# Top.net
KiCad netlist of a schematic drawn in Altium Designer
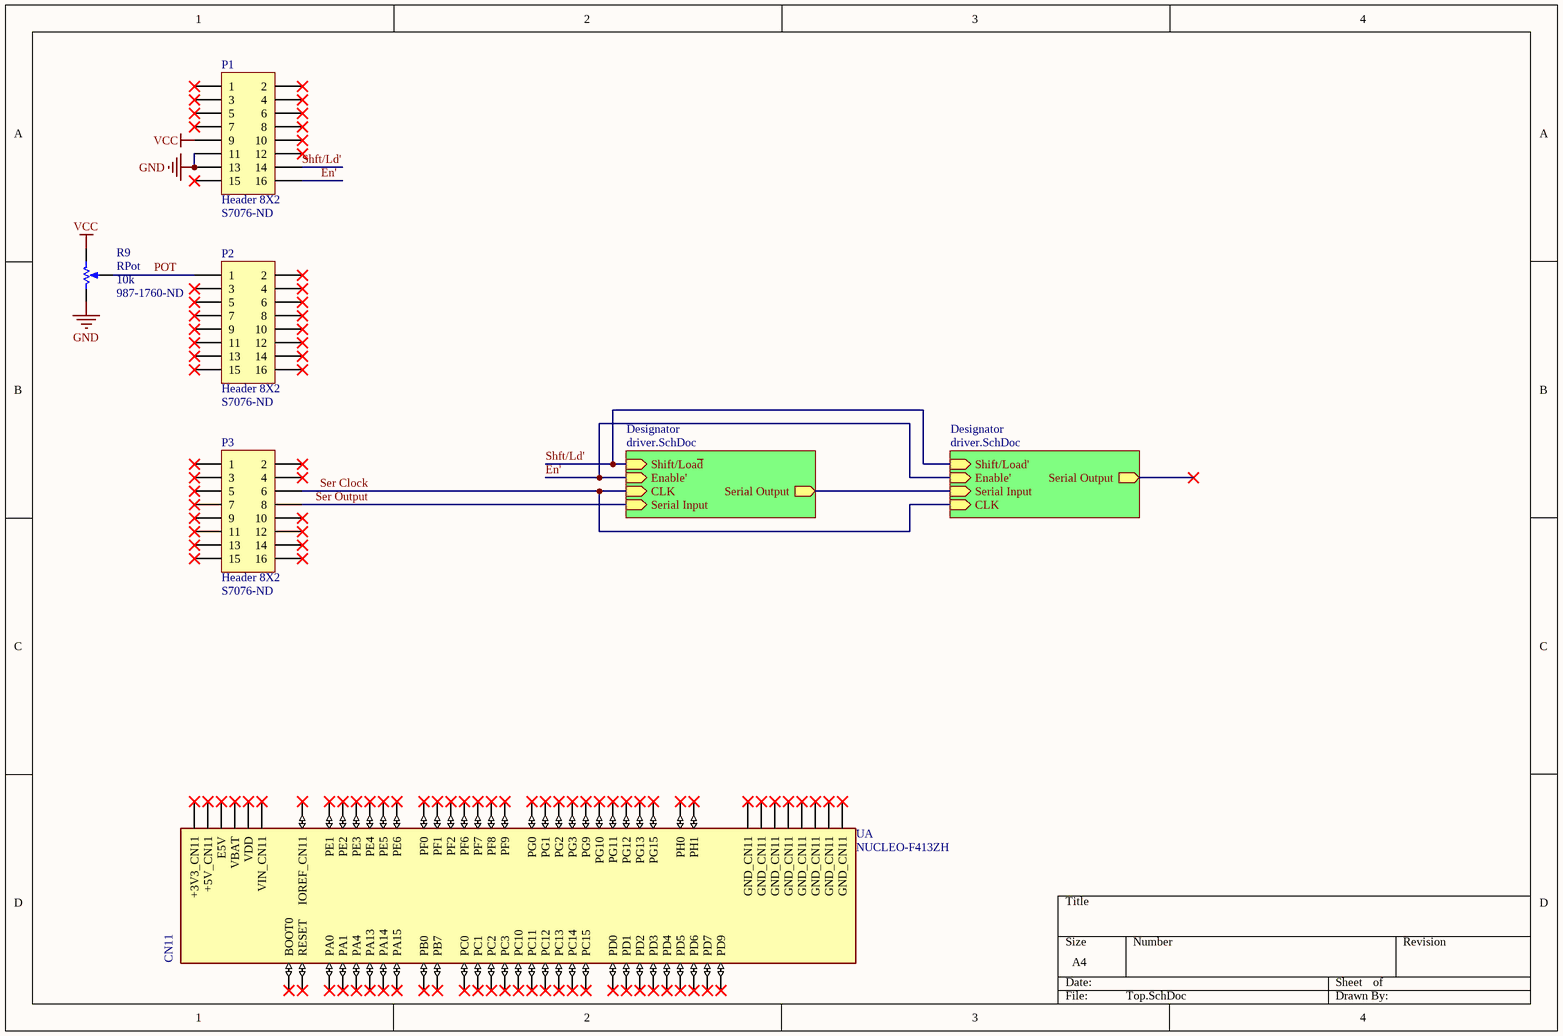
[diagram p0: Top.SchDoc]

(export (version "E")
  (design (tool "Eeschema 10.0.6"))
  (components
    (comp (ref "P1")
      (value "Header 8X2")
      (footprint "HDR2X8")
      (description "Header, 8-Pin, Dual row")
      (fields (field (name "SUPPLIER PART NUMBER 1") "S7076-ND") (field (name "PUBLISHER") "Altium Limited"))
      (libsource (lib "Miscellaneous Connectors") (part "Header 8X2"))
    )
    (comp (ref "P2")
      (value "Header 8X2")
      (footprint "HDR2X8")
      (description "Header, 8-Pin, Dual row")
      (fields (field (name "SUPPLIER PART NUMBER 1") "S7076-ND") (field (name "PUBLISHER") "Altium Limited"))
      (libsource (lib "Miscellaneous Connectors") (part "Header 8X2"))
    )
    (comp (ref "P3")
      (value "Header 8X2")
      (footprint "HDR2X8")
      (description "Header, 8-Pin, Dual row")
      (fields (field (name "SUPPLIER PART NUMBER 1") "S7076-ND") (field (name "PUBLISHER") "Altium Limited"))
      (libsource (lib "Miscellaneous Connectors") (part "Header 8X2"))
    )
    (comp (ref "R9")
      (value "RPot")
      (footprint "VR5")
      (description "Potentiometer")
      (fields
        (field (name "ALTIUM_VALUE") "10k")
        (field (name "SUPPLIER PART NUMBER 1") "987-1760-ND")
        (field (name "PUBLISHER") "Altium Limited")
      )
      (libsource (lib "Miscellaneous Devices") (part "RPot"))
    )
    (comp (ref "U")
      (value "NUCLEO-F413ZH")
      (footprint "ST_NUCLEO-F413ZH")
      (fields (field (name "MF") "STMicroelectronics"))
      (libsource (lib "NUCLEO-F413ZH") (part "NUCLEO-F413ZH"))
    )
  )
  (nets
    (net (code "1") (name "/En'") (class "Default")
      (node (ref "P1") (pin "16") (pinfunction "16_16") (pintype "passive"))
    )
    (net (code "2") (name "/POT") (class "Default")
      (node (ref "P2") (pin "1") (pinfunction "1_1") (pintype "passive"))
      (node (ref "R9") (pin "3") (pinfunction "TAP_3") (pintype "passive"))
    )
    (net (code "3") (name "/Ser Clock") (class "Default")
      (node (ref "P3") (pin "6") (pinfunction "6_6") (pintype "passive"))
    )
    (net (code "4") (name "/Ser Output") (class "Default")
      (node (ref "P3") (pin "8") (pinfunction "8_8") (pintype "passive"))
    )
    (net (code "7") (name "/Shft{slash}Ld'") (class "Default")
      (node (ref "P1") (pin "14") (pinfunction "14_14") (pintype "passive"))
    )
    (net (code "8") (name "GND") (class "Default")
      (node (ref "P1") (pin "11") (pinfunction "11_11") (pintype "passive"))
      (node (ref "P1") (pin "13") (pinfunction "13_13") (pintype "passive"))
      (node (ref "R9") (pin "2") (pinfunction "BOT_2") (pintype "passive"))
    )
    (net (code "9") (name "VCC") (class "Default")
      (node (ref "P1") (pin "9") (pinfunction "9_9") (pintype "passive"))
      (node (ref "R9") (pin "1") (pinfunction "TOP_1") (pintype "passive"))
    )
    (net (code "10") (name "unconnected-(P1-Pad1)") (class "Default")
      (node (ref "P1") (pin "1") (pinfunction "1_1") (pintype "passive+no_connect"))
    )
    (net (code "11") (name "unconnected-(P1-Pad2)") (class "Default")
      (node (ref "P1") (pin "2") (pinfunction "2_2") (pintype "passive+no_connect"))
    )
    (net (code "12") (name "unconnected-(P1-Pad3)") (class "Default")
      (node (ref "P1") (pin "3") (pinfunction "3_3") (pintype "passive+no_connect"))
    )
    (net (code "13") (name "unconnected-(P1-Pad4)") (class "Default")
      (node (ref "P1") (pin "4") (pinfunction "4_4") (pintype "passive+no_connect"))
    )
    (net (code "14") (name "unconnected-(P1-Pad5)") (class "Default")
      (node (ref "P1") (pin "5") (pinfunction "5_5") (pintype "passive+no_connect"))
    )
    (net (code "15") (name "unconnected-(P1-Pad6)") (class "Default")
      (node (ref "P1") (pin "6") (pinfunction "6_6") (pintype "passive+no_connect"))
    )
    (net (code "16") (name "unconnected-(P1-Pad7)") (class "Default")
      (node (ref "P1") (pin "7") (pinfunction "7_7") (pintype "passive+no_connect"))
    )
    (net (code "17") (name "unconnected-(P1-Pad8)") (class "Default")
      (node (ref "P1") (pin "8") (pinfunction "8_8") (pintype "passive+no_connect"))
    )
    (net (code "18") (name "unconnected-(P1-Pad10)") (class "Default")
      (node (ref "P1") (pin "10") (pinfunction "10_10") (pintype "passive+no_connect"))
    )
    (net (code "19") (name "unconnected-(P1-Pad12)") (class "Default")
      (node (ref "P1") (pin "12") (pinfunction "12_12") (pintype "passive+no_connect"))
    )
    (net (code "20") (name "unconnected-(P1-Pad15)") (class "Default")
      (node (ref "P1") (pin "15") (pinfunction "15_15") (pintype "passive+no_connect"))
    )
    (net (code "21") (name "unconnected-(P2-Pad2)") (class "Default")
      (node (ref "P2") (pin "2") (pinfunction "2_2") (pintype "passive+no_connect"))
    )
    (net (code "22") (name "unconnected-(P2-Pad3)") (class "Default")
      (node (ref "P2") (pin "3") (pinfunction "3_3") (pintype "passive+no_connect"))
    )
    (net (code "23") (name "unconnected-(P2-Pad4)") (class "Default")
      (node (ref "P2") (pin "4") (pinfunction "4_4") (pintype "passive+no_connect"))
    )
    (net (code "24") (name "unconnected-(P2-Pad5)") (class "Default")
      (node (ref "P2") (pin "5") (pinfunction "5_5") (pintype "passive+no_connect"))
    )
    (net (code "25") (name "unconnected-(P2-Pad6)") (class "Default")
      (node (ref "P2") (pin "6") (pinfunction "6_6") (pintype "passive+no_connect"))
    )
    (net (code "26") (name "unconnected-(P2-Pad7)") (class "Default")
      (node (ref "P2") (pin "7") (pinfunction "7_7") (pintype "passive+no_connect"))
    )
    (net (code "27") (name "unconnected-(P2-Pad8)") (class "Default")
      (node (ref "P2") (pin "8") (pinfunction "8_8") (pintype "passive+no_connect"))
    )
    (net (code "28") (name "unconnected-(P2-Pad9)") (class "Default")
      (node (ref "P2") (pin "9") (pinfunction "9_9") (pintype "passive+no_connect"))
    )
    (net (code "29") (name "unconnected-(P2-Pad10)") (class "Default")
      (node (ref "P2") (pin "10") (pinfunction "10_10") (pintype "passive+no_connect"))
    )
    (net (code "30") (name "unconnected-(P2-Pad11)") (class "Default")
      (node (ref "P2") (pin "11") (pinfunction "11_11") (pintype "passive+no_connect"))
    )
    (net (code "31") (name "unconnected-(P2-Pad12)") (class "Default")
      (node (ref "P2") (pin "12") (pinfunction "12_12") (pintype "passive+no_connect"))
    )
    (net (code "32") (name "unconnected-(P2-Pad13)") (class "Default")
      (node (ref "P2") (pin "13") (pinfunction "13_13") (pintype "passive+no_connect"))
    )
    (net (code "33") (name "unconnected-(P2-Pad14)") (class "Default")
      (node (ref "P2") (pin "14") (pinfunction "14_14") (pintype "passive+no_connect"))
    )
    (net (code "34") (name "unconnected-(P2-Pad15)") (class "Default")
      (node (ref "P2") (pin "15") (pinfunction "15_15") (pintype "passive+no_connect"))
    )
    (net (code "35") (name "unconnected-(P2-Pad16)") (class "Default")
      (node (ref "P2") (pin "16") (pinfunction "16_16") (pintype "passive+no_connect"))
    )
    (net (code "36") (name "unconnected-(P3-Pad1)") (class "Default")
      (node (ref "P3") (pin "1") (pinfunction "1_1") (pintype "passive+no_connect"))
    )
    (net (code "37") (name "unconnected-(P3-Pad2)") (class "Default")
      (node (ref "P3") (pin "2") (pinfunction "2_2") (pintype "passive+no_connect"))
    )
    (net (code "38") (name "unconnected-(P3-Pad3)") (class "Default")
      (node (ref "P3") (pin "3") (pinfunction "3_3") (pintype "passive+no_connect"))
    )
    (net (code "39") (name "unconnected-(P3-Pad4)") (class "Default")
      (node (ref "P3") (pin "4") (pinfunction "4_4") (pintype "passive+no_connect"))
    )
    (net (code "40") (name "unconnected-(P3-Pad5)") (class "Default")
      (node (ref "P3") (pin "5") (pinfunction "5_5") (pintype "passive+no_connect"))
    )
    (net (code "41") (name "unconnected-(P3-Pad7)") (class "Default")
      (node (ref "P3") (pin "7") (pinfunction "7_7") (pintype "passive+no_connect"))
    )
    (net (code "42") (name "unconnected-(P3-Pad9)") (class "Default")
      (node (ref "P3") (pin "9") (pinfunction "9_9") (pintype "passive+no_connect"))
    )
    (net (code "43") (name "unconnected-(P3-Pad10)") (class "Default")
      (node (ref "P3") (pin "10") (pinfunction "10_10") (pintype "passive+no_connect"))
    )
    (net (code "44") (name "unconnected-(P3-Pad11)") (class "Default")
      (node (ref "P3") (pin "11") (pinfunction "11_11") (pintype "passive+no_connect"))
    )
    (net (code "45") (name "unconnected-(P3-Pad12)") (class "Default")
      (node (ref "P3") (pin "12") (pinfunction "12_12") (pintype "passive+no_connect"))
    )
    (net (code "46") (name "unconnected-(P3-Pad13)") (class "Default")
      (node (ref "P3") (pin "13") (pinfunction "13_13") (pintype "passive+no_connect"))
    )
    (net (code "47") (name "unconnected-(P3-Pad14)") (class "Default")
      (node (ref "P3") (pin "14") (pinfunction "14_14") (pintype "passive+no_connect"))
    )
    (net (code "48") (name "unconnected-(P3-Pad15)") (class "Default")
      (node (ref "P3") (pin "15") (pinfunction "15_15") (pintype "passive+no_connect"))
    )
    (net (code "49") (name "unconnected-(P3-Pad16)") (class "Default")
      (node (ref "P3") (pin "16") (pinfunction "16_16") (pintype "passive+no_connect"))
    )
    (net (code "50") (name "unconnected-(UA-+3V3_CN11-PadCN11_16)") (class "Default")
      (node (ref "U") (pin "CN11_16") (pinfunction "+3V3_CN11_CN11_16") (pintype "power_in+no_connect"))
    )
    (net (code "51") (name "unconnected-(UA-+5V_CN11-PadCN11_18)") (class "Default")
      (node (ref "U") (pin "CN11_18") (pinfunction "+5V_CN11_CN11_18") (pintype "power_in+no_connect"))
    )
    (net (code "52") (name "unconnected-(UA-BOOT0-PadCN11_7)") (class "Default")
      (node (ref "U") (pin "CN11_7") (pinfunction "BOOT0_CN11_7") (pintype "bidirectional+no_connect"))
    )
    (net (code "53") (name "unconnected-(UA-E5V-PadCN11_6)") (class "Default")
      (node (ref "U") (pin "CN11_6") (pinfunction "E5V_CN11_6") (pintype "power_in+no_connect"))
    )
    (net (code "54") (name "unconnected-(UA-GND_CN11-PadCN11_8)") (class "Default")
      (node (ref "U") (pin "CN11_8") (pinfunction "GND_CN11_CN11_8") (pintype "power_in+no_connect"))
    )
    (net (code "55") (name "unconnected-(UA-GND_CN11-PadCN11_19)") (class "Default")
      (node (ref "U") (pin "CN11_19") (pinfunction "GND_CN11_CN11_19") (pintype "power_in+no_connect"))
    )
    (net (code "56") (name "unconnected-(UA-GND_CN11-PadCN11_20)") (class "Default")
      (node (ref "U") (pin "CN11_20") (pinfunction "GND_CN11_CN11_20") (pintype "power_in+no_connect"))
    )
    (net (code "57") (name "unconnected-(UA-GND_CN11-PadCN11_22)") (class "Default")
      (node (ref "U") (pin "CN11_22") (pinfunction "GND_CN11_CN11_22") (pintype "power_in+no_connect"))
    )
    (net (code "58") (name "unconnected-(UA-GND_CN11-PadCN11_49)") (class "Default")
      (node (ref "U") (pin "CN11_49") (pinfunction "GND_CN11_CN11_49") (pintype "power_in+no_connect"))
    )
    (net (code "59") (name "unconnected-(UA-GND_CN11-PadCN11_60)") (class "Default")
      (node (ref "U") (pin "CN11_60") (pinfunction "GND_CN11_CN11_60") (pintype "power_in+no_connect"))
    )
    (net (code "60") (name "unconnected-(UA-GND_CN11-PadCN11_71)") (class "Default")
      (node (ref "U") (pin "CN11_71") (pinfunction "GND_CN11_CN11_71") (pintype "power_in+no_connect"))
    )
    (net (code "61") (name "unconnected-(UA-GND_CN11-PadCN11_72)") (class "Default")
      (node (ref "U") (pin "CN11_72") (pinfunction "GND_CN11_CN11_72") (pintype "power_in+no_connect"))
    )
    (net (code "62") (name "unconnected-(UA-IOREF_CN11-PadCN11_12)") (class "Default")
      (node (ref "U") (pin "CN11_12") (pinfunction "IOREF_CN11_CN11_12") (pintype "bidirectional+no_connect"))
    )
    (net (code "63") (name "unconnected-(UA-PA0-PadCN11_28)") (class "Default")
      (node (ref "U") (pin "CN11_28") (pinfunction "PA0_CN11_28") (pintype "bidirectional+no_connect"))
    )
    (net (code "64") (name "unconnected-(UA-PA1-PadCN11_30)") (class "Default")
      (node (ref "U") (pin "CN11_30") (pinfunction "PA1_CN11_30") (pintype "bidirectional+no_connect"))
    )
    (net (code "65") (name "unconnected-(UA-PA4-PadCN11_32)") (class "Default")
      (node (ref "U") (pin "CN11_32") (pinfunction "PA4_CN11_32") (pintype "bidirectional+no_connect"))
    )
    (net (code "66") (name "unconnected-(UA-PA13-PadCN11_13)") (class "Default")
      (node (ref "U") (pin "CN11_13") (pinfunction "PA13_CN11_13") (pintype "bidirectional+no_connect"))
    )
    (net (code "67") (name "unconnected-(UA-PA14-PadCN11_15)") (class "Default")
      (node (ref "U") (pin "CN11_15") (pinfunction "PA14_CN11_15") (pintype "bidirectional+no_connect"))
    )
    (net (code "68") (name "unconnected-(UA-PA15-PadCN11_17)") (class "Default")
      (node (ref "U") (pin "CN11_17") (pinfunction "PA15_CN11_17") (pintype "bidirectional+no_connect"))
    )
    (net (code "69") (name "unconnected-(UA-PB0-PadCN11_34)") (class "Default")
      (node (ref "U") (pin "CN11_34") (pinfunction "PB0_CN11_34") (pintype "bidirectional+no_connect"))
    )
    (net (code "70") (name "unconnected-(UA-PB7-PadCN11_21)") (class "Default")
      (node (ref "U") (pin "CN11_21") (pinfunction "PB7_CN11_21") (pintype "bidirectional+no_connect"))
    )
    (net (code "71") (name "unconnected-(UA-PC0-PadCN11_38)") (class "Default")
      (node (ref "U") (pin "CN11_38") (pinfunction "PC0_CN11_38") (pintype "bidirectional+no_connect"))
    )
    (net (code "72") (name "unconnected-(UA-PC1-PadCN11_36)") (class "Default")
      (node (ref "U") (pin "CN11_36") (pinfunction "PC1_CN11_36") (pintype "bidirectional+no_connect"))
    )
    (net (code "73") (name "unconnected-(UA-PC2-PadCN11_35)") (class "Default")
      (node (ref "U") (pin "CN11_35") (pinfunction "PC2_CN11_35") (pintype "bidirectional+no_connect"))
    )
    (net (code "74") (name "unconnected-(UA-PC3-PadCN11_37)") (class "Default")
      (node (ref "U") (pin "CN11_37") (pinfunction "PC3_CN11_37") (pintype "bidirectional+no_connect"))
    )
    (net (code "75") (name "unconnected-(UA-PC10-PadCN11_1)") (class "Default")
      (node (ref "U") (pin "CN11_1") (pinfunction "PC10_CN11_1") (pintype "bidirectional+no_connect"))
    )
    (net (code "76") (name "unconnected-(UA-PC11-PadCN11_2)") (class "Default")
      (node (ref "U") (pin "CN11_2") (pinfunction "PC11_CN11_2") (pintype "bidirectional+no_connect"))
    )
    (net (code "77") (name "unconnected-(UA-PC12-PadCN11_3)") (class "Default")
      (node (ref "U") (pin "CN11_3") (pinfunction "PC12_CN11_3") (pintype "bidirectional+no_connect"))
    )
    (net (code "78") (name "unconnected-(UA-PC13-PadCN11_23)") (class "Default")
      (node (ref "U") (pin "CN11_23") (pinfunction "PC13_CN11_23") (pintype "bidirectional+no_connect"))
    )
    (net (code "79") (name "unconnected-(UA-PC14-PadCN11_25)") (class "Default")
      (node (ref "U") (pin "CN11_25") (pinfunction "PC14_CN11_25") (pintype "bidirectional+no_connect"))
    )
    (net (code "80") (name "unconnected-(UA-PC15-PadCN11_27)") (class "Default")
      (node (ref "U") (pin "CN11_27") (pinfunction "PC15_CN11_27") (pintype "bidirectional+no_connect"))
    )
    (net (code "81") (name "unconnected-(UA-PD0-PadCN11_57)") (class "Default")
      (node (ref "U") (pin "CN11_57") (pinfunction "PD0_CN11_57") (pintype "bidirectional+no_connect"))
    )
    (net (code "82") (name "unconnected-(UA-PD1-PadCN11_55)") (class "Default")
      (node (ref "U") (pin "CN11_55") (pinfunction "PD1_CN11_55") (pintype "bidirectional+no_connect"))
    )
    (net (code "83") (name "unconnected-(UA-PD2-PadCN11_4)") (class "Default")
      (node (ref "U") (pin "CN11_4") (pinfunction "PD2_CN11_4") (pintype "bidirectional+no_connect"))
    )
    (net (code "84") (name "unconnected-(UA-PD3-PadCN11_40)") (class "Default")
      (node (ref "U") (pin "CN11_40") (pinfunction "PD3_CN11_40") (pintype "bidirectional+no_connect"))
    )
    (net (code "85") (name "unconnected-(UA-PD4-PadCN11_39)") (class "Default")
      (node (ref "U") (pin "CN11_39") (pinfunction "PD4_CN11_39") (pintype "bidirectional+no_connect"))
    )
    (net (code "86") (name "unconnected-(UA-PD5-PadCN11_41)") (class "Default")
      (node (ref "U") (pin "CN11_41") (pinfunction "PD5_CN11_41") (pintype "bidirectional+no_connect"))
    )
    (net (code "87") (name "unconnected-(UA-PD6-PadCN11_43)") (class "Default")
      (node (ref "U") (pin "CN11_43") (pinfunction "PD6_CN11_43") (pintype "bidirectional+no_connect"))
    )
    (net (code "88") (name "unconnected-(UA-PD7-PadCN11_45)") (class "Default")
      (node (ref "U") (pin "CN11_45") (pinfunction "PD7_CN11_45") (pintype "bidirectional+no_connect"))
    )
    (net (code "89") (name "unconnected-(UA-PD9-PadCN11_69)") (class "Default")
      (node (ref "U") (pin "CN11_69") (pinfunction "PD9_CN11_69") (pintype "bidirectional+no_connect"))
    )
    (net (code "90") (name "unconnected-(UA-PE1-PadCN11_61)") (class "Default")
      (node (ref "U") (pin "CN11_61") (pinfunction "PE1_CN11_61") (pintype "bidirectional+no_connect"))
    )
    (net (code "91") (name "unconnected-(UA-PE2-PadCN11_46)") (class "Default")
      (node (ref "U") (pin "CN11_46") (pinfunction "PE2_CN11_46") (pintype "bidirectional+no_connect"))
    )
    (net (code "92") (name "unconnected-(UA-PE3-PadCN11_47)") (class "Default")
      (node (ref "U") (pin "CN11_47") (pinfunction "PE3_CN11_47") (pintype "bidirectional+no_connect"))
    )
    (net (code "93") (name "unconnected-(UA-PE4-PadCN11_48)") (class "Default")
      (node (ref "U") (pin "CN11_48") (pinfunction "PE4_CN11_48") (pintype "bidirectional+no_connect"))
    )
    (net (code "94") (name "unconnected-(UA-PE5-PadCN11_50)") (class "Default")
      (node (ref "U") (pin "CN11_50") (pinfunction "PE5_CN11_50") (pintype "bidirectional+no_connect"))
    )
    (net (code "95") (name "unconnected-(UA-PE6-PadCN11_62)") (class "Default")
      (node (ref "U") (pin "CN11_62") (pinfunction "PE6_CN11_62") (pintype "bidirectional+no_connect"))
    )
    (net (code "96") (name "unconnected-(UA-PF0-PadCN11_53)") (class "Default")
      (node (ref "U") (pin "CN11_53") (pinfunction "PF0_CN11_53") (pintype "bidirectional+no_connect"))
    )
    (net (code "97") (name "unconnected-(UA-PF1-PadCN11_51)") (class "Default")
      (node (ref "U") (pin "CN11_51") (pinfunction "PF1_CN11_51") (pintype "bidirectional+no_connect"))
    )
    (net (code "98") (name "unconnected-(UA-PF2-PadCN11_52)") (class "Default")
      (node (ref "U") (pin "CN11_52") (pinfunction "PF2_CN11_52") (pintype "bidirectional+no_connect"))
    )
    (net (code "99") (name "unconnected-(UA-PF6-PadCN11_9)") (class "Default")
      (node (ref "U") (pin "CN11_9") (pinfunction "PF6_CN11_9") (pintype "bidirectional+no_connect"))
    )
    (net (code "100") (name "unconnected-(UA-PF7-PadCN11_11)") (class "Default")
      (node (ref "U") (pin "CN11_11") (pinfunction "PF7_CN11_11") (pintype "bidirectional+no_connect"))
    )
    (net (code "101") (name "unconnected-(UA-PF8-PadCN11_54)") (class "Default")
      (node (ref "U") (pin "CN11_54") (pinfunction "PF8_CN11_54") (pintype "bidirectional+no_connect"))
    )
    (net (code "102") (name "unconnected-(UA-PF9-PadCN11_56)") (class "Default")
      (node (ref "U") (pin "CN11_56") (pinfunction "PF9_CN11_56") (pintype "bidirectional+no_connect"))
    )
    (net (code "103") (name "unconnected-(UA-PG0-PadCN11_59)") (class "Default")
      (node (ref "U") (pin "CN11_59") (pinfunction "PG0_CN11_59") (pintype "bidirectional+no_connect"))
    )
    (net (code "104") (name "unconnected-(UA-PG1-PadCN11_58)") (class "Default")
      (node (ref "U") (pin "CN11_58") (pinfunction "PG1_CN11_58") (pintype "bidirectional+no_connect"))
    )
    (net (code "105") (name "unconnected-(UA-PG2-PadCN11_42)") (class "Default")
      (node (ref "U") (pin "CN11_42") (pinfunction "PG2_CN11_42") (pintype "bidirectional+no_connect"))
    )
    (net (code "106") (name "unconnected-(UA-PG3-PadCN11_44)") (class "Default")
      (node (ref "U") (pin "CN11_44") (pinfunction "PG3_CN11_44") (pintype "bidirectional+no_connect"))
    )
    (net (code "107") (name "unconnected-(UA-PG9-PadCN11_63)") (class "Default")
      (node (ref "U") (pin "CN11_63") (pinfunction "PG9_CN11_63") (pintype "bidirectional+no_connect"))
    )
    (net (code "108") (name "unconnected-(UA-PG10-PadCN11_66)") (class "Default")
      (node (ref "U") (pin "CN11_66") (pinfunction "PG10_CN11_66") (pintype "bidirectional+no_connect"))
    )
    (net (code "109") (name "unconnected-(UA-PG11-PadCN11_70)") (class "Default")
      (node (ref "U") (pin "CN11_70") (pinfunction "PG11_CN11_70") (pintype "bidirectional+no_connect"))
    )
    (net (code "110") (name "unconnected-(UA-PG12-PadCN11_65)") (class "Default")
      (node (ref "U") (pin "CN11_65") (pinfunction "PG12_CN11_65") (pintype "bidirectional+no_connect"))
    )
    (net (code "111") (name "unconnected-(UA-PG13-PadCN11_68)") (class "Default")
      (node (ref "U") (pin "CN11_68") (pinfunction "PG13_CN11_68") (pintype "bidirectional+no_connect"))
    )
    (net (code "112") (name "unconnected-(UA-PG15-PadCN11_64)") (class "Default")
      (node (ref "U") (pin "CN11_64") (pinfunction "PG15_CN11_64") (pintype "bidirectional+no_connect"))
    )
    (net (code "113") (name "unconnected-(UA-PH0-PadCN11_29)") (class "Default")
      (node (ref "U") (pin "CN11_29") (pinfunction "PH0_CN11_29") (pintype "bidirectional+no_connect"))
    )
    (net (code "114") (name "unconnected-(UA-PH1-PadCN11_31)") (class "Default")
      (node (ref "U") (pin "CN11_31") (pinfunction "PH1_CN11_31") (pintype "bidirectional+no_connect"))
    )
    (net (code "115") (name "unconnected-(UA-RESET-PadCN11_14)") (class "Default")
      (node (ref "U") (pin "CN11_14") (pinfunction "RESET_CN11_14") (pintype "bidirectional+no_connect"))
    )
    (net (code "116") (name "unconnected-(UA-VBAT-PadCN11_33)") (class "Default")
      (node (ref "U") (pin "CN11_33") (pinfunction "VBAT_CN11_33") (pintype "power_in+no_connect"))
    )
    (net (code "117") (name "unconnected-(UA-VDD-PadCN11_5)") (class "Default")
      (node (ref "U") (pin "CN11_5") (pinfunction "VDD_CN11_5") (pintype "power_in+no_connect"))
    )
    (net (code "118") (name "unconnected-(UA-VIN_CN11-PadCN11_24)") (class "Default")
      (node (ref "U") (pin "CN11_24") (pinfunction "VIN_CN11_CN11_24") (pintype "power_in+no_connect"))
    )
  )
)
